# rc2014_16550b.net
KiCad netlist of a schematic drawn in EAGLE
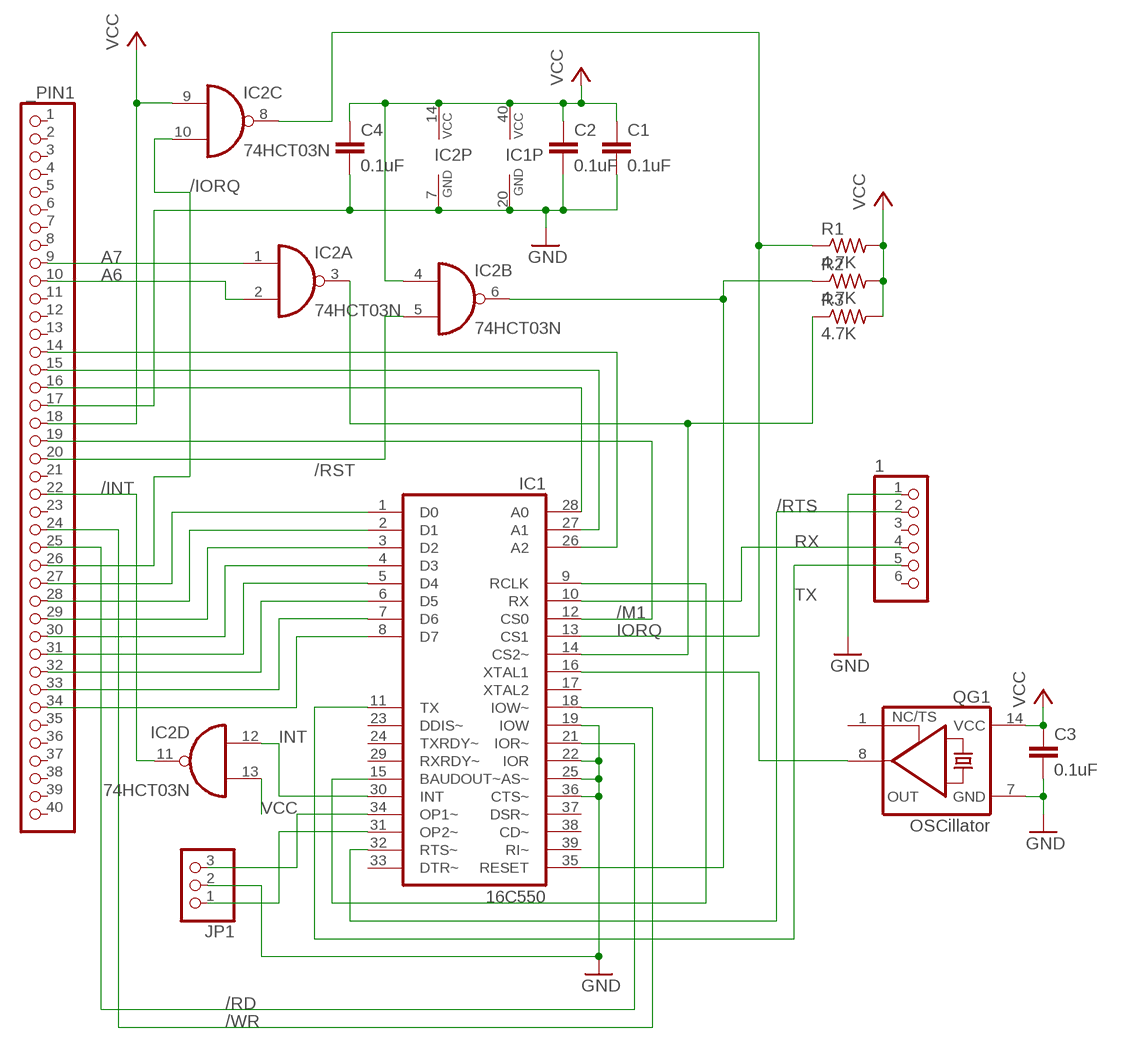
[diagram p0: schematic, sheet 1]

(export (version "E")
  (design (tool "Eeschema 10.0.6"))
  (components
    (comp (ref "1")
      (value "PINHD-1X6")
      (footprint "eagle-import:1X06")
      (libsource (lib "eagle-import") (part "PINHD-1X6"))
    )
    (comp (ref "C1")
      (value "0.1uF")
      (footprint "eagle-import:C050-024X044")
      (libsource (lib "eagle-import") (part "C-EU050-024X044"))
    )
    (comp (ref "C2")
      (value "0.1uF")
      (footprint "eagle-import:C050-024X044")
      (libsource (lib "eagle-import") (part "C-EU050-024X044"))
    )
    (comp (ref "C3")
      (value "0.1uF")
      (footprint "eagle-import:C050-024X044")
      (libsource (lib "eagle-import") (part "C-EU050-024X044"))
    )
    (comp (ref "C4")
      (value "0.1uF")
      (footprint "eagle-import:C050-024X044")
      (libsource (lib "eagle-import") (part "C-EU050-024X044"))
    )
    (comp (ref "IC1")
      (value "16C550")
      (footprint "eagle-import:DIL40")
      (fields (field (name "MPN") "ST16C450CP40"))
      (libsource (lib "eagle-import") (part "XR-16C550P"))
    )
    (comp (ref "IC2")
      (value "74HCT03N")
      (footprint "eagle-import:DIL14")
      (libsource (lib "eagle-import") (part "7400NHCT"))
    )
    (comp (ref "JP1")
      (value "PINHD-1X3")
      (footprint "eagle-import:1X03")
      (libsource (lib "eagle-import") (part "PINHD-1X3"))
    )
    (comp (ref "QG1")
      (value "OSCillator")
      (footprint "eagle-import:DIL14S")
      (libsource (lib "eagle-import") (part "XO-14"))
    )
    (comp (ref "R1")
      (value "4.7K")
      (footprint "eagle-import:0207_10")
      (libsource (lib "eagle-import") (part "R-US_0207/10"))
    )
    (comp (ref "R2")
      (value "4.7K")
      (footprint "eagle-import:0207_10")
      (libsource (lib "eagle-import") (part "R-US_0207/10"))
    )
    (comp (ref "R3")
      (value "4.7K")
      (footprint "eagle-import:0207_10")
      (libsource (lib "eagle-import") (part "R-US_0207/10"))
    )
    (comp (ref "_PIN1")
      (value "PINHD-1X40")
      (footprint "eagle-import:1X40")
      (libsource (lib "eagle-import") (part "PINHD-1X40"))
    )
  )
  (nets
    (net (code "1") (name "/A6") (class "Default")
      (node (ref "IC2") (pin "2") (pinfunction "I1_2") (pintype "input"))
      (node (ref "_PIN1") (pin "10") (pinfunction "10_10") (pintype "passive"))
    )
    (net (code "2") (name "/A7") (class "Default")
      (node (ref "IC2") (pin "1") (pinfunction "I0_1") (pintype "input"))
      (node (ref "_PIN1") (pin "9") (pinfunction "9_9") (pintype "passive"))
    )
    (net (code "3") (name "/INT") (class "Default")
      (node (ref "IC1") (pin "30") (pinfunction "INT_30") (pintype "output"))
      (node (ref "IC2") (pin "12") (pinfunction "I0_12") (pintype "input"))
    )
    (net (code "4") (name "/IORQ") (class "Default")
      (node (ref "IC1") (pin "13") (pinfunction "CS1_13") (pintype "input"))
      (node (ref "IC2") (pin "8") (pinfunction "O_8") (pintype "output"))
      (node (ref "R1") (pin "1") (pinfunction "1_1") (pintype "passive"))
    )
    (net (code "5") (name "/RX") (class "Default")
      (node (ref "1") (pin "4") (pinfunction "4_4") (pintype "passive"))
      (node (ref "IC1") (pin "10") (pinfunction "RX_10") (pintype "input"))
    )
    (net (code "6") (name "/TX") (class "Default")
      (node (ref "1") (pin "5") (pinfunction "5_5") (pintype "passive"))
      (node (ref "IC1") (pin "11") (pinfunction "TX_11") (pintype "output"))
    )
    (net (code "7") (name "/{slash}INT") (class "Default")
      (node (ref "IC2") (pin "11") (pinfunction "O_11") (pintype "output"))
      (node (ref "_PIN1") (pin "22") (pinfunction "22_22") (pintype "passive"))
    )
    (net (code "8") (name "/{slash}IORQ") (class "Default")
      (node (ref "IC2") (pin "10") (pinfunction "I1_10") (pintype "input"))
      (node (ref "_PIN1") (pin "26") (pinfunction "26_26") (pintype "passive"))
    )
    (net (code "9") (name "/{slash}M1") (class "Default")
      (node (ref "IC1") (pin "12") (pinfunction "CS0_12") (pintype "input"))
      (node (ref "_PIN1") (pin "19") (pinfunction "19_19") (pintype "passive"))
    )
    (net (code "10") (name "/{slash}RD") (class "Default")
      (node (ref "IC1") (pin "21") (pinfunction "IOR~{}_21") (pintype "input"))
      (node (ref "_PIN1") (pin "25") (pinfunction "25_25") (pintype "passive"))
    )
    (net (code "11") (name "/{slash}RST") (class "Default")
      (node (ref "IC2") (pin "5") (pinfunction "I1_5") (pintype "input"))
      (node (ref "_PIN1") (pin "20") (pinfunction "20_20") (pintype "passive"))
    )
    (net (code "12") (name "/{slash}RTS") (class "Default")
      (node (ref "1") (pin "2") (pinfunction "2_2") (pintype "passive"))
      (node (ref "IC1") (pin "32") (pinfunction "RTS~{}_32") (pintype "output"))
    )
    (net (code "13") (name "/{slash}WR") (class "Default")
      (node (ref "IC1") (pin "18") (pinfunction "IOW~{}_18") (pintype "input"))
      (node (ref "_PIN1") (pin "24") (pinfunction "24_24") (pintype "passive"))
    )
    (net (code "14") (name "GND") (class "Default")
      (node (ref "1") (pin "1") (pinfunction "1_1") (pintype "passive"))
      (node (ref "C1") (pin "2") (pinfunction "2_2") (pintype "passive"))
      (node (ref "C2") (pin "2") (pinfunction "2_2") (pintype "passive"))
      (node (ref "C3") (pin "2") (pinfunction "2_2") (pintype "passive"))
      (node (ref "C4") (pin "2") (pinfunction "2_2") (pintype "passive"))
      (node (ref "IC1") (pin "19") (pinfunction "IOW_19") (pintype "input"))
      (node (ref "IC1") (pin "20") (pinfunction "GND_20") (pintype "power_in"))
      (node (ref "IC1") (pin "22") (pinfunction "IOR_22") (pintype "input"))
      (node (ref "IC1") (pin "25") (pinfunction "AS~{}_25") (pintype "input"))
      (node (ref "IC1") (pin "36") (pinfunction "CTS~{}_36") (pintype "input"))
      (node (ref "IC2") (pin "7") (pinfunction "GND_7") (pintype "power_in"))
      (node (ref "JP1") (pin "2") (pinfunction "2_2") (pintype "passive"))
      (node (ref "QG1") (pin "7") (pinfunction "GND_7") (pintype "power_in"))
      (node (ref "_PIN1") (pin "17") (pinfunction "17_17") (pintype "passive"))
    )
    (net (code "15") (name "Net-(IC1A-A0)") (class "Default")
      (node (ref "IC1") (pin "28") (pinfunction "A0_28") (pintype "input"))
      (node (ref "_PIN1") (pin "16") (pinfunction "16_16") (pintype "passive"))
    )
    (net (code "16") (name "Net-(IC1A-A1)") (class "Default")
      (node (ref "IC1") (pin "27") (pinfunction "A1_27") (pintype "input"))
      (node (ref "_PIN1") (pin "15") (pinfunction "15_15") (pintype "passive"))
    )
    (net (code "17") (name "Net-(IC1A-A2)") (class "Default")
      (node (ref "IC1") (pin "26") (pinfunction "A2_26") (pintype "input"))
      (node (ref "_PIN1") (pin "14") (pinfunction "14_14") (pintype "passive"))
    )
    (net (code "18") (name "Net-(IC1A-BAUDOUT~{})") (class "Default")
      (node (ref "IC1") (pin "15") (pinfunction "BAUDOUT~{}_15") (pintype "output"))
      (node (ref "IC1") (pin "9") (pinfunction "RCLK_9") (pintype "input"))
    )
    (net (code "19") (name "Net-(IC1A-CS2~{})") (class "Default")
      (node (ref "IC1") (pin "14") (pinfunction "CS2~{}_14") (pintype "input"))
      (node (ref "IC2") (pin "3") (pinfunction "O_3") (pintype "output"))
      (node (ref "R3") (pin "1") (pinfunction "1_1") (pintype "passive"))
    )
    (net (code "20") (name "Net-(IC1A-D0)") (class "Default")
      (node (ref "IC1") (pin "1") (pinfunction "D0_1") (pintype "bidirectional"))
      (node (ref "_PIN1") (pin "27") (pinfunction "27_27") (pintype "passive"))
    )
    (net (code "21") (name "Net-(IC1A-D1)") (class "Default")
      (node (ref "IC1") (pin "2") (pinfunction "D1_2") (pintype "bidirectional"))
      (node (ref "_PIN1") (pin "28") (pinfunction "28_28") (pintype "passive"))
    )
    (net (code "22") (name "Net-(IC1A-D2)") (class "Default")
      (node (ref "IC1") (pin "3") (pinfunction "D2_3") (pintype "bidirectional"))
      (node (ref "_PIN1") (pin "29") (pinfunction "29_29") (pintype "passive"))
    )
    (net (code "23") (name "Net-(IC1A-D3)") (class "Default")
      (node (ref "IC1") (pin "4") (pinfunction "D3_4") (pintype "bidirectional"))
      (node (ref "_PIN1") (pin "30") (pinfunction "30_30") (pintype "passive"))
    )
    (net (code "24") (name "Net-(IC1A-D4)") (class "Default")
      (node (ref "IC1") (pin "5") (pinfunction "D4_5") (pintype "bidirectional"))
      (node (ref "_PIN1") (pin "31") (pinfunction "31_31") (pintype "passive"))
    )
    (net (code "25") (name "Net-(IC1A-D5)") (class "Default")
      (node (ref "IC1") (pin "6") (pinfunction "D5_6") (pintype "bidirectional"))
      (node (ref "_PIN1") (pin "32") (pinfunction "32_32") (pintype "passive"))
    )
    (net (code "26") (name "Net-(IC1A-D6)") (class "Default")
      (node (ref "IC1") (pin "7") (pinfunction "D6_7") (pintype "bidirectional"))
      (node (ref "_PIN1") (pin "33") (pinfunction "33_33") (pintype "passive"))
    )
    (net (code "27") (name "Net-(IC1A-D7)") (class "Default")
      (node (ref "IC1") (pin "8") (pinfunction "D7_8") (pintype "bidirectional"))
      (node (ref "_PIN1") (pin "34") (pinfunction "34_34") (pintype "passive"))
    )
    (net (code "28") (name "Net-(IC1A-OP1~{})") (class "Default")
      (node (ref "IC1") (pin "34") (pinfunction "OP1~{}_34") (pintype "output"))
      (node (ref "JP1") (pin "3") (pinfunction "3_3") (pintype "passive"))
    )
    (net (code "29") (name "Net-(IC1A-OP2~{})") (class "Default")
      (node (ref "IC1") (pin "31") (pinfunction "OP2~{}_31") (pintype "output"))
      (node (ref "JP1") (pin "1") (pinfunction "1_1") (pintype "passive"))
    )
    (net (code "30") (name "Net-(IC1A-RESET)") (class "Default")
      (node (ref "IC1") (pin "35") (pinfunction "RESET_35") (pintype "input"))
      (node (ref "IC2") (pin "6") (pinfunction "O_6") (pintype "output"))
      (node (ref "R2") (pin "1") (pinfunction "1_1") (pintype "passive"))
    )
    (net (code "31") (name "Net-(IC1A-XTAL1)") (class "Default")
      (node (ref "IC1") (pin "16") (pinfunction "XTAL1_16") (pintype "input"))
      (node (ref "QG1") (pin "8") (pinfunction "OUT_8") (pintype "output"))
    )
    (net (code "32") (name "VCC") (class "Default")
      (node (ref "C1") (pin "1") (pinfunction "1_1") (pintype "passive"))
      (node (ref "C2") (pin "1") (pinfunction "1_1") (pintype "passive"))
      (node (ref "C3") (pin "1") (pinfunction "1_1") (pintype "passive"))
      (node (ref "C4") (pin "1") (pinfunction "1_1") (pintype "passive"))
      (node (ref "IC1") (pin "40") (pinfunction "VCC_40") (pintype "power_in"))
      (node (ref "IC2") (pin "13") (pinfunction "I1_13") (pintype "input"))
      (node (ref "IC2") (pin "14") (pinfunction "VCC_14") (pintype "power_in"))
      (node (ref "IC2") (pin "4") (pinfunction "I0_4") (pintype "input"))
      (node (ref "IC2") (pin "9") (pinfunction "I0_9") (pintype "input"))
      (node (ref "QG1") (pin "14") (pinfunction "VCC_14") (pintype "power_in"))
      (node (ref "R1") (pin "2") (pinfunction "2_2") (pintype "passive"))
      (node (ref "R2") (pin "2") (pinfunction "2_2") (pintype "passive"))
      (node (ref "R3") (pin "2") (pinfunction "2_2") (pintype "passive"))
      (node (ref "_PIN1") (pin "18") (pinfunction "18_18") (pintype "passive"))
    )
    (net (code "33") (name "unconnected-(1-Pad3)") (class "Default")
      (node (ref "1") (pin "3") (pinfunction "3_3") (pintype "passive"))
    )
    (net (code "34") (name "unconnected-(1-Pad6)") (class "Default")
      (node (ref "1") (pin "6") (pinfunction "6_6") (pintype "passive"))
    )
    (net (code "35") (name "unconnected-(IC1A-CD~{}-Pad38)") (class "Default")
      (node (ref "IC1") (pin "38") (pinfunction "CD~{}_38") (pintype "input"))
    )
    (net (code "36") (name "unconnected-(IC1A-DDIS~{}-Pad23)") (class "Default")
      (node (ref "IC1") (pin "23") (pinfunction "DDIS~{}_23") (pintype "output"))
    )
    (net (code "37") (name "unconnected-(IC1A-DSR~{}-Pad37)") (class "Default")
      (node (ref "IC1") (pin "37") (pinfunction "DSR~{}_37") (pintype "input"))
    )
    (net (code "38") (name "unconnected-(IC1A-DTR~{}-Pad33)") (class "Default")
      (node (ref "IC1") (pin "33") (pinfunction "DTR~{}_33") (pintype "output"))
    )
    (net (code "39") (name "unconnected-(IC1A-RI~{}-Pad39)") (class "Default")
      (node (ref "IC1") (pin "39") (pinfunction "RI~{}_39") (pintype "input"))
    )
    (net (code "40") (name "unconnected-(IC1A-RXRDY~{}-Pad29)") (class "Default")
      (node (ref "IC1") (pin "29") (pinfunction "RXRDY~{}_29") (pintype "output"))
    )
    (net (code "41") (name "unconnected-(IC1A-TXRDY~{}-Pad24)") (class "Default")
      (node (ref "IC1") (pin "24") (pinfunction "TXRDY~{}_24") (pintype "output"))
    )
    (net (code "42") (name "unconnected-(IC1A-XTAL2-Pad17)") (class "Default")
      (node (ref "IC1") (pin "17") (pinfunction "XTAL2_17") (pintype "input"))
    )
    (net (code "43") (name "unconnected-(QG1-TS-Pad1)") (class "Default")
      (node (ref "QG1") (pin "1") (pinfunction "TS_1") (pintype "passive"))
    )
    (net (code "44") (name "unconnected-(_PIN1-Pad1)") (class "Default")
      (node (ref "_PIN1") (pin "1") (pinfunction "1_1") (pintype "passive"))
    )
    (net (code "45") (name "unconnected-(_PIN1-Pad2)") (class "Default")
      (node (ref "_PIN1") (pin "2") (pinfunction "2_2") (pintype "passive"))
    )
    (net (code "46") (name "unconnected-(_PIN1-Pad3)") (class "Default")
      (node (ref "_PIN1") (pin "3") (pinfunction "3_3") (pintype "passive"))
    )
    (net (code "47") (name "unconnected-(_PIN1-Pad4)") (class "Default")
      (node (ref "_PIN1") (pin "4") (pinfunction "4_4") (pintype "passive"))
    )
    (net (code "48") (name "unconnected-(_PIN1-Pad5)") (class "Default")
      (node (ref "_PIN1") (pin "5") (pinfunction "5_5") (pintype "passive"))
    )
    (net (code "49") (name "unconnected-(_PIN1-Pad6)") (class "Default")
      (node (ref "_PIN1") (pin "6") (pinfunction "6_6") (pintype "passive"))
    )
    (net (code "50") (name "unconnected-(_PIN1-Pad7)") (class "Default")
      (node (ref "_PIN1") (pin "7") (pinfunction "7_7") (pintype "passive"))
    )
    (net (code "51") (name "unconnected-(_PIN1-Pad8)") (class "Default")
      (node (ref "_PIN1") (pin "8") (pinfunction "8_8") (pintype "passive"))
    )
    (net (code "52") (name "unconnected-(_PIN1-Pad11)") (class "Default")
      (node (ref "_PIN1") (pin "11") (pinfunction "11_11") (pintype "passive"))
    )
    (net (code "53") (name "unconnected-(_PIN1-Pad12)") (class "Default")
      (node (ref "_PIN1") (pin "12") (pinfunction "12_12") (pintype "passive"))
    )
    (net (code "54") (name "unconnected-(_PIN1-Pad13)") (class "Default")
      (node (ref "_PIN1") (pin "13") (pinfunction "13_13") (pintype "passive"))
    )
    (net (code "55") (name "unconnected-(_PIN1-Pad21)") (class "Default")
      (node (ref "_PIN1") (pin "21") (pinfunction "21_21") (pintype "passive"))
    )
    (net (code "56") (name "unconnected-(_PIN1-Pad23)") (class "Default")
      (node (ref "_PIN1") (pin "23") (pinfunction "23_23") (pintype "passive"))
    )
    (net (code "57") (name "unconnected-(_PIN1-Pad35)") (class "Default")
      (node (ref "_PIN1") (pin "35") (pinfunction "35_35") (pintype "passive"))
    )
    (net (code "58") (name "unconnected-(_PIN1-Pad36)") (class "Default")
      (node (ref "_PIN1") (pin "36") (pinfunction "36_36") (pintype "passive"))
    )
    (net (code "59") (name "unconnected-(_PIN1-Pad37)") (class "Default")
      (node (ref "_PIN1") (pin "37") (pinfunction "37_37") (pintype "passive"))
    )
    (net (code "60") (name "unconnected-(_PIN1-Pad38)") (class "Default")
      (node (ref "_PIN1") (pin "38") (pinfunction "38_38") (pintype "passive"))
    )
    (net (code "61") (name "unconnected-(_PIN1-Pad39)") (class "Default")
      (node (ref "_PIN1") (pin "39") (pinfunction "39_39") (pintype "passive"))
    )
    (net (code "62") (name "unconnected-(_PIN1-Pad40)") (class "Default")
      (node (ref "_PIN1") (pin "40") (pinfunction "40_40") (pintype "passive"))
    )
  )
)
